# mixer2_post_layout_2.net
KiCad netlist of a schematic drawn in EAGLE
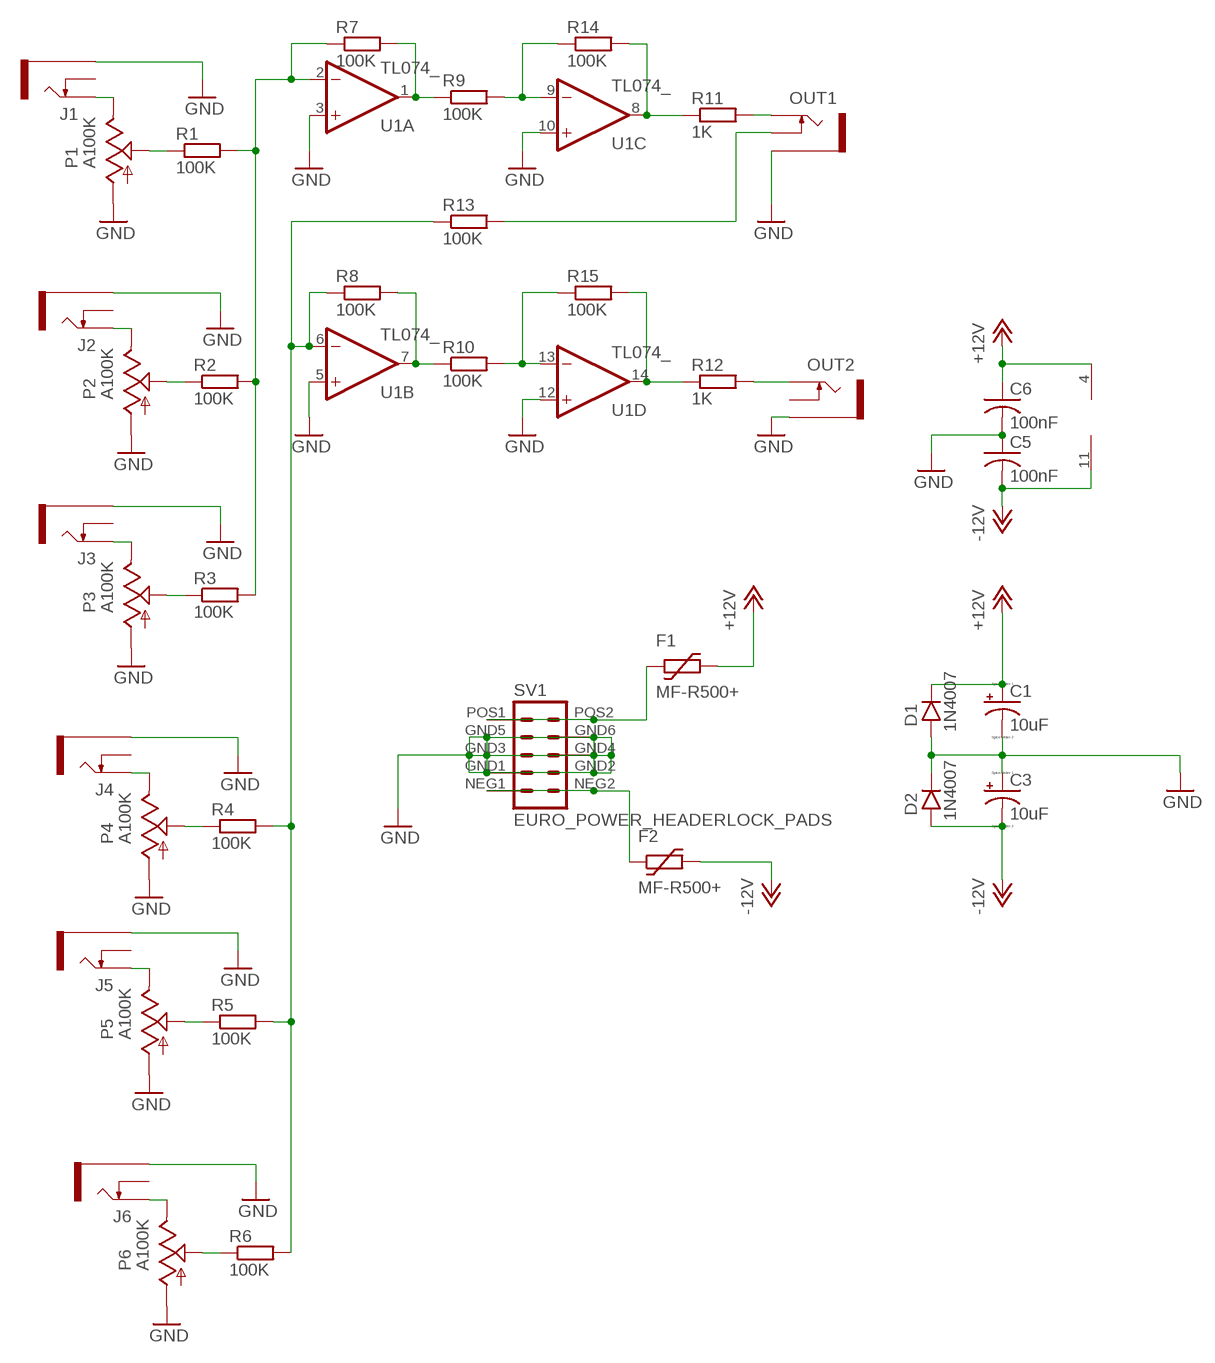
[diagram p0: schematic, sheet 1]

(export (version "E")
  (design (tool "Eeschema 10.0.6"))
  (components
    (comp (ref "C1")
      (value "10uF")
      (footprint "eagle-import:E2,5-7")
      (libsource (lib "eagle-import") (part "CPOL-USE2.5-7"))
    )
    (comp (ref "C3")
      (value "10uF")
      (footprint "eagle-import:E2,5-7")
      (libsource (lib "eagle-import") (part "CPOL-USE2.5-7"))
    )
    (comp (ref "C5")
      (value "100nF")
      (footprint "eagle-import:C075-032X103")
      (libsource (lib "eagle-import") (part "C-US075-032X103"))
    )
    (comp (ref "C6")
      (value "100nF")
      (footprint "eagle-import:C075-032X103")
      (libsource (lib "eagle-import") (part "C-US075-032X103"))
    )
    (comp (ref "D1")
      (value "1N4007")
      (footprint "eagle-import:DO41-3")
      (libsource (lib "eagle-import") (part "1N400X.3"))
    )
    (comp (ref "D2")
      (value "1N4007")
      (footprint "eagle-import:DO41-3")
      (libsource (lib "eagle-import") (part "1N400X.3"))
    )
    (comp (ref "F1")
      (value "MF-R500+")
      (footprint "eagle-import:BOURNS-MF-R")
      (libsource (lib "eagle-import") (part "MF-R500+"))
    )
    (comp (ref "F2")
      (value "MF-R500+")
      (footprint "eagle-import:BOURNS-MF-R")
      (libsource (lib "eagle-import") (part "MF-R500+"))
    )
    (comp (ref "J1")
      (value "THONKICONNNEW")
      (footprint "eagle-import:WQP-PJ301M-12_JACK")
      (libsource (lib "eagle-import") (part "THONKICONNNEW"))
    )
    (comp (ref "J2")
      (value "THONKICONNNEW")
      (footprint "eagle-import:WQP-PJ301M-12_JACK")
      (libsource (lib "eagle-import") (part "THONKICONNNEW"))
    )
    (comp (ref "J3")
      (value "THONKICONNNEW")
      (footprint "eagle-import:WQP-PJ301M-12_JACK")
      (libsource (lib "eagle-import") (part "THONKICONNNEW"))
    )
    (comp (ref "J4")
      (value "THONKICONNNEW")
      (footprint "eagle-import:WQP-PJ301M-12_JACK")
      (libsource (lib "eagle-import") (part "THONKICONNNEW"))
    )
    (comp (ref "J5")
      (value "THONKICONNNEW")
      (footprint "eagle-import:WQP-PJ301M-12_JACK")
      (libsource (lib "eagle-import") (part "THONKICONNNEW"))
    )
    (comp (ref "J6")
      (value "THONKICONNNEW")
      (footprint "eagle-import:WQP-PJ301M-12_JACK")
      (libsource (lib "eagle-import") (part "THONKICONNNEW"))
    )
    (comp (ref "OUT1")
      (value "THONKICONNNEW")
      (footprint "eagle-import:WQP-PJ301M-12_JACK")
      (libsource (lib "eagle-import") (part "THONKICONNNEW"))
    )
    (comp (ref "OUT2")
      (value "THONKICONNNEW")
      (footprint "eagle-import:WQP-PJ301M-12_JACK")
      (libsource (lib "eagle-import") (part "THONKICONNNEW"))
    )
    (comp (ref "P1")
      (value "A100K")
      (footprint "eagle-import:9MM_SNAP-IN_POT")
      (libsource (lib "eagle-import") (part "9MM_SNAP-IN_POT_"))
    )
    (comp (ref "P2")
      (value "A100K")
      (footprint "eagle-import:9MM_SNAP-IN_POT")
      (libsource (lib "eagle-import") (part "9MM_SNAP-IN_POT_"))
    )
    (comp (ref "P3")
      (value "A100K")
      (footprint "eagle-import:9MM_SNAP-IN_POT")
      (libsource (lib "eagle-import") (part "9MM_SNAP-IN_POT_"))
    )
    (comp (ref "P4")
      (value "A100K")
      (footprint "eagle-import:9MM_SNAP-IN_POT")
      (libsource (lib "eagle-import") (part "9MM_SNAP-IN_POT_"))
    )
    (comp (ref "P5")
      (value "A100K")
      (footprint "eagle-import:9MM_SNAP-IN_POT")
      (libsource (lib "eagle-import") (part "9MM_SNAP-IN_POT_"))
    )
    (comp (ref "P6")
      (value "A100K")
      (footprint "eagle-import:9MM_SNAP-IN_POT")
      (libsource (lib "eagle-import") (part "9MM_SNAP-IN_POT_"))
    )
    (comp (ref "R1")
      (value "100K")
      (footprint "eagle-import:7MM_RESISTOR")
      (libsource (lib "eagle-import") (part "RESISTOR7MM"))
    )
    (comp (ref "R2")
      (value "100K")
      (footprint "eagle-import:7MM_RESISTOR")
      (libsource (lib "eagle-import") (part "RESISTOR7MM"))
    )
    (comp (ref "R3")
      (value "100K")
      (footprint "eagle-import:7MM_RESISTOR")
      (libsource (lib "eagle-import") (part "RESISTOR7MM"))
    )
    (comp (ref "R4")
      (value "100K")
      (footprint "eagle-import:7MM_RESISTOR")
      (libsource (lib "eagle-import") (part "RESISTOR7MM"))
    )
    (comp (ref "R5")
      (value "100K")
      (footprint "eagle-import:7MM_RESISTOR")
      (libsource (lib "eagle-import") (part "RESISTOR7MM"))
    )
    (comp (ref "R6")
      (value "100K")
      (footprint "eagle-import:7MM_RESISTOR")
      (libsource (lib "eagle-import") (part "RESISTOR7MM"))
    )
    (comp (ref "R7")
      (value "100K")
      (footprint "eagle-import:7MM_RESISTOR")
      (libsource (lib "eagle-import") (part "RESISTOR7MM"))
    )
    (comp (ref "R8")
      (value "100K")
      (footprint "eagle-import:7MM_RESISTOR")
      (libsource (lib "eagle-import") (part "RESISTOR7MM"))
    )
    (comp (ref "R9")
      (value "100K")
      (footprint "eagle-import:7MM_RESISTOR")
      (libsource (lib "eagle-import") (part "RESISTOR7MM"))
    )
    (comp (ref "R10")
      (value "100K")
      (footprint "eagle-import:7MM_RESISTOR")
      (libsource (lib "eagle-import") (part "RESISTOR7MM"))
    )
    (comp (ref "R11")
      (value "1K")
      (footprint "eagle-import:7MM_RESISTOR")
      (libsource (lib "eagle-import") (part "RESISTOR7MM"))
    )
    (comp (ref "R12")
      (value "1K")
      (footprint "eagle-import:7MM_RESISTOR")
      (libsource (lib "eagle-import") (part "RESISTOR7MM"))
    )
    (comp (ref "R13")
      (value "100K")
      (footprint "eagle-import:7MM_RESISTOR")
      (libsource (lib "eagle-import") (part "RESISTOR7MM"))
    )
    (comp (ref "R14")
      (value "100K")
      (footprint "eagle-import:7MM_RESISTOR")
      (libsource (lib "eagle-import") (part "RESISTOR7MM"))
    )
    (comp (ref "R15")
      (value "100K")
      (footprint "eagle-import:7MM_RESISTOR")
      (libsource (lib "eagle-import") (part "RESISTOR7MM"))
    )
    (comp (ref "SV1")
      (value "EURO_POWER_HEADERLOCK_PADS")
      (footprint "eagle-import:EURO_PWR_HEADER_LOCK")
      (libsource (lib "eagle-import") (part "EURO_POWER_HEADERLOCK_PADS"))
    )
    (comp (ref "U1")
      (value "TL074_")
      (footprint "eagle-import:DIL14")
      (libsource (lib "eagle-import") (part "TL074_"))
    )
  )
  (nets
    (net (code "1") (name "+12V") (class "Default")
      (node (ref "C1") (pin "+") (pinfunction "+_+") (pintype "passive"))
      (node (ref "C6") (pin "1") (pinfunction "1_1") (pintype "passive"))
      (node (ref "D1") (pin "C") (pinfunction "C_C") (pintype "passive"))
      (node (ref "F1") (pin "P$2") (pinfunction "2_P$2") (pintype "passive"))
      (node (ref "U1") (pin "4") (pinfunction "V+_4") (pintype "power_in"))
    )
    (net (code "2") (name "-12V") (class "Default")
      (node (ref "C3") (pin "-") (pinfunction "-_-") (pintype "passive"))
      (node (ref "C5") (pin "2") (pinfunction "2_2") (pintype "passive"))
      (node (ref "D2") (pin "A") (pinfunction "A_A") (pintype "passive"))
      (node (ref "F2") (pin "P$2") (pinfunction "2_P$2") (pintype "passive"))
      (node (ref "U1") (pin "11") (pinfunction "V-_11") (pintype "power_in"))
    )
    (net (code "3") (name "GND") (class "Default")
      (node (ref "C1") (pin "-") (pinfunction "-_-") (pintype "passive"))
      (node (ref "C3") (pin "+") (pinfunction "+_+") (pintype "passive"))
      (node (ref "C5") (pin "1") (pinfunction "1_1") (pintype "passive"))
      (node (ref "C6") (pin "2") (pinfunction "2_2") (pintype "passive"))
      (node (ref "D1") (pin "A") (pinfunction "A_A") (pintype "passive"))
      (node (ref "D2") (pin "C") (pinfunction "C_C") (pintype "passive"))
      (node (ref "J1") (pin "P$3_SLEEVE") (pinfunction "SLEEVE_P$3_SLEEVE") (pintype "passive"))
      (node (ref "J2") (pin "P$3_SLEEVE") (pinfunction "SLEEVE_P$3_SLEEVE") (pintype "passive"))
      (node (ref "J3") (pin "P$3_SLEEVE") (pinfunction "SLEEVE_P$3_SLEEVE") (pintype "passive"))
      (node (ref "J4") (pin "P$3_SLEEVE") (pinfunction "SLEEVE_P$3_SLEEVE") (pintype "passive"))
      (node (ref "J5") (pin "P$3_SLEEVE") (pinfunction "SLEEVE_P$3_SLEEVE") (pintype "passive"))
      (node (ref "J6") (pin "P$3_SLEEVE") (pinfunction "SLEEVE_P$3_SLEEVE") (pintype "passive"))
      (node (ref "OUT1") (pin "P$3_SLEEVE") (pinfunction "SLEEVE_P$3_SLEEVE") (pintype "passive"))
      (node (ref "OUT2") (pin "P$3_SLEEVE") (pinfunction "SLEEVE_P$3_SLEEVE") (pintype "passive"))
      (node (ref "P1") (pin "1") (pinfunction "A_1") (pintype "passive"))
      (node (ref "P2") (pin "1") (pinfunction "A_1") (pintype "passive"))
      (node (ref "P3") (pin "1") (pinfunction "A_1") (pintype "passive"))
      (node (ref "P4") (pin "1") (pinfunction "A_1") (pintype "passive"))
      (node (ref "P5") (pin "1") (pinfunction "A_1") (pintype "passive"))
      (node (ref "P6") (pin "1") (pinfunction "A_1") (pintype "passive"))
      (node (ref "SV1") (pin "GND1") (pinfunction "4_GND1") (pintype "passive"))
      (node (ref "SV1") (pin "GND2") (pinfunction "3_GND2") (pintype "passive"))
      (node (ref "SV1") (pin "GND3") (pinfunction "6_GND3") (pintype "passive"))
      (node (ref "SV1") (pin "GND4") (pinfunction "5_GND4") (pintype "passive"))
      (node (ref "SV1") (pin "GND5") (pinfunction "8_GND5") (pintype "passive"))
      (node (ref "SV1") (pin "GND6") (pinfunction "7_GND6") (pintype "passive"))
      (node (ref "U1") (pin "10") (pinfunction "+IN_10") (pintype "input"))
      (node (ref "U1") (pin "12") (pinfunction "+IN_12") (pintype "input"))
      (node (ref "U1") (pin "3") (pinfunction "+IN_3") (pintype "input"))
      (node (ref "U1") (pin "5") (pinfunction "+IN_5") (pintype "input"))
    )
    (net (code "4") (name "Net-(F1-1)") (class "Default")
      (node (ref "F1") (pin "P$1") (pinfunction "1_P$1") (pintype "passive"))
      (node (ref "SV1") (pin "POS1") (pinfunction "10_POS1") (pintype "passive"))
      (node (ref "SV1") (pin "POS2") (pinfunction "9_POS2") (pintype "passive"))
    )
    (net (code "5") (name "Net-(F2-1)") (class "Default")
      (node (ref "F2") (pin "P$1") (pinfunction "1_P$1") (pintype "passive"))
      (node (ref "SV1") (pin "NEG1") (pinfunction "2_NEG1") (pintype "passive"))
      (node (ref "SV1") (pin "NEG2") (pinfunction "1_NEG2") (pintype "passive"))
    )
    (net (code "6") (name "Net-(J1-TIP)") (class "Default")
      (node (ref "J1") (pin "P$1_TIP") (pinfunction "TIP_P$1_TIP") (pintype "passive"))
      (node (ref "P1") (pin "3") (pinfunction "E_3") (pintype "passive"))
    )
    (net (code "7") (name "Net-(J2-TIP)") (class "Default")
      (node (ref "J2") (pin "P$1_TIP") (pinfunction "TIP_P$1_TIP") (pintype "passive"))
      (node (ref "P2") (pin "3") (pinfunction "E_3") (pintype "passive"))
    )
    (net (code "8") (name "Net-(J3-TIP)") (class "Default")
      (node (ref "J3") (pin "P$1_TIP") (pinfunction "TIP_P$1_TIP") (pintype "passive"))
      (node (ref "P3") (pin "3") (pinfunction "E_3") (pintype "passive"))
    )
    (net (code "9") (name "Net-(J4-TIP)") (class "Default")
      (node (ref "J4") (pin "P$1_TIP") (pinfunction "TIP_P$1_TIP") (pintype "passive"))
      (node (ref "P4") (pin "3") (pinfunction "E_3") (pintype "passive"))
    )
    (net (code "10") (name "Net-(J5-TIP)") (class "Default")
      (node (ref "J5") (pin "P$1_TIP") (pinfunction "TIP_P$1_TIP") (pintype "passive"))
      (node (ref "P5") (pin "3") (pinfunction "E_3") (pintype "passive"))
    )
    (net (code "11") (name "Net-(J6-TIP)") (class "Default")
      (node (ref "J6") (pin "P$1_TIP") (pinfunction "TIP_P$1_TIP") (pintype "passive"))
      (node (ref "P6") (pin "3") (pinfunction "E_3") (pintype "passive"))
    )
    (net (code "12") (name "Net-(OUT1-SWITCH)") (class "Default")
      (node (ref "OUT1") (pin "P$2_SWITCH") (pinfunction "SWITCH_P$2_SWITCH") (pintype "passive"))
      (node (ref "R13") (pin "2") (pinfunction "2_2") (pintype "passive"))
    )
    (net (code "13") (name "Net-(OUT1-TIP)") (class "Default")
      (node (ref "OUT1") (pin "P$1_TIP") (pinfunction "TIP_P$1_TIP") (pintype "passive"))
      (node (ref "R11") (pin "2") (pinfunction "2_2") (pintype "passive"))
    )
    (net (code "14") (name "Net-(OUT2-TIP)") (class "Default")
      (node (ref "OUT2") (pin "P$1_TIP") (pinfunction "TIP_P$1_TIP") (pintype "passive"))
      (node (ref "R12") (pin "2") (pinfunction "2_2") (pintype "passive"))
    )
    (net (code "15") (name "Net-(P1-S)") (class "Default")
      (node (ref "P1") (pin "2") (pinfunction "S_2") (pintype "passive"))
      (node (ref "R1") (pin "1") (pinfunction "1_1") (pintype "passive"))
    )
    (net (code "16") (name "Net-(P2-S)") (class "Default")
      (node (ref "P2") (pin "2") (pinfunction "S_2") (pintype "passive"))
      (node (ref "R2") (pin "1") (pinfunction "1_1") (pintype "passive"))
    )
    (net (code "17") (name "Net-(P3-S)") (class "Default")
      (node (ref "P3") (pin "2") (pinfunction "S_2") (pintype "passive"))
      (node (ref "R3") (pin "1") (pinfunction "1_1") (pintype "passive"))
    )
    (net (code "18") (name "Net-(P4-S)") (class "Default")
      (node (ref "P4") (pin "2") (pinfunction "S_2") (pintype "passive"))
      (node (ref "R4") (pin "1") (pinfunction "1_1") (pintype "passive"))
    )
    (net (code "19") (name "Net-(P5-S)") (class "Default")
      (node (ref "P5") (pin "2") (pinfunction "S_2") (pintype "passive"))
      (node (ref "R5") (pin "1") (pinfunction "1_1") (pintype "passive"))
    )
    (net (code "20") (name "Net-(P6-S)") (class "Default")
      (node (ref "P6") (pin "2") (pinfunction "S_2") (pintype "passive"))
      (node (ref "R6") (pin "1") (pinfunction "1_1") (pintype "passive"))
    )
    (net (code "21") (name "Net-(U1A--IN)") (class "Default")
      (node (ref "R1") (pin "2") (pinfunction "2_2") (pintype "passive"))
      (node (ref "R2") (pin "2") (pinfunction "2_2") (pintype "passive"))
      (node (ref "R3") (pin "2") (pinfunction "2_2") (pintype "passive"))
      (node (ref "R7") (pin "1") (pinfunction "1_1") (pintype "passive"))
      (node (ref "U1") (pin "2") (pinfunction "-IN_2") (pintype "input"))
    )
    (net (code "22") (name "Net-(U1A-OUT)") (class "Default")
      (node (ref "R7") (pin "2") (pinfunction "2_2") (pintype "passive"))
      (node (ref "R9") (pin "1") (pinfunction "1_1") (pintype "passive"))
      (node (ref "U1") (pin "1") (pinfunction "OUT_1") (pintype "output"))
    )
    (net (code "23") (name "Net-(U1B--IN)") (class "Default")
      (node (ref "R13") (pin "1") (pinfunction "1_1") (pintype "passive"))
      (node (ref "R4") (pin "2") (pinfunction "2_2") (pintype "passive"))
      (node (ref "R5") (pin "2") (pinfunction "2_2") (pintype "passive"))
      (node (ref "R6") (pin "2") (pinfunction "2_2") (pintype "passive"))
      (node (ref "R8") (pin "1") (pinfunction "1_1") (pintype "passive"))
      (node (ref "U1") (pin "6") (pinfunction "-IN_6") (pintype "input"))
    )
    (net (code "24") (name "Net-(U1B-OUT)") (class "Default")
      (node (ref "R10") (pin "1") (pinfunction "1_1") (pintype "passive"))
      (node (ref "R8") (pin "2") (pinfunction "2_2") (pintype "passive"))
      (node (ref "U1") (pin "7") (pinfunction "OUT_7") (pintype "output"))
    )
    (net (code "25") (name "Net-(U1C--IN)") (class "Default")
      (node (ref "R14") (pin "1") (pinfunction "1_1") (pintype "passive"))
      (node (ref "R9") (pin "2") (pinfunction "2_2") (pintype "passive"))
      (node (ref "U1") (pin "9") (pinfunction "-IN_9") (pintype "input"))
    )
    (net (code "26") (name "Net-(U1C-OUT)") (class "Default")
      (node (ref "R11") (pin "1") (pinfunction "1_1") (pintype "passive"))
      (node (ref "R14") (pin "2") (pinfunction "2_2") (pintype "passive"))
      (node (ref "U1") (pin "8") (pinfunction "OUT_8") (pintype "output"))
    )
    (net (code "27") (name "Net-(U1D--IN)") (class "Default")
      (node (ref "R10") (pin "2") (pinfunction "2_2") (pintype "passive"))
      (node (ref "R15") (pin "1") (pinfunction "1_1") (pintype "passive"))
      (node (ref "U1") (pin "13") (pinfunction "-IN_13") (pintype "input"))
    )
    (net (code "28") (name "Net-(U1D-OUT)") (class "Default")
      (node (ref "R12") (pin "1") (pinfunction "1_1") (pintype "passive"))
      (node (ref "R15") (pin "2") (pinfunction "2_2") (pintype "passive"))
      (node (ref "U1") (pin "14") (pinfunction "OUT_14") (pintype "output"))
    )
    (net (code "29") (name "unconnected-(J1-SWITCH-PadP$2_SWITCH)") (class "Default")
      (node (ref "J1") (pin "P$2_SWITCH") (pinfunction "SWITCH_P$2_SWITCH") (pintype "passive"))
    )
    (net (code "30") (name "unconnected-(J2-SWITCH-PadP$2_SWITCH)") (class "Default")
      (node (ref "J2") (pin "P$2_SWITCH") (pinfunction "SWITCH_P$2_SWITCH") (pintype "passive"))
    )
    (net (code "31") (name "unconnected-(J3-SWITCH-PadP$2_SWITCH)") (class "Default")
      (node (ref "J3") (pin "P$2_SWITCH") (pinfunction "SWITCH_P$2_SWITCH") (pintype "passive"))
    )
    (net (code "32") (name "unconnected-(J4-SWITCH-PadP$2_SWITCH)") (class "Default")
      (node (ref "J4") (pin "P$2_SWITCH") (pinfunction "SWITCH_P$2_SWITCH") (pintype "passive"))
    )
    (net (code "33") (name "unconnected-(J5-SWITCH-PadP$2_SWITCH)") (class "Default")
      (node (ref "J5") (pin "P$2_SWITCH") (pinfunction "SWITCH_P$2_SWITCH") (pintype "passive"))
    )
    (net (code "34") (name "unconnected-(J6-SWITCH-PadP$2_SWITCH)") (class "Default")
      (node (ref "J6") (pin "P$2_SWITCH") (pinfunction "SWITCH_P$2_SWITCH") (pintype "passive"))
    )
    (net (code "35") (name "unconnected-(OUT2-SWITCH-PadP$2_SWITCH)") (class "Default")
      (node (ref "OUT2") (pin "P$2_SWITCH") (pinfunction "SWITCH_P$2_SWITCH") (pintype "passive"))
    )
  )
)
